# 13_1_Port-Backplane.net
KiCad netlist of a schematic drawn in EAGLE
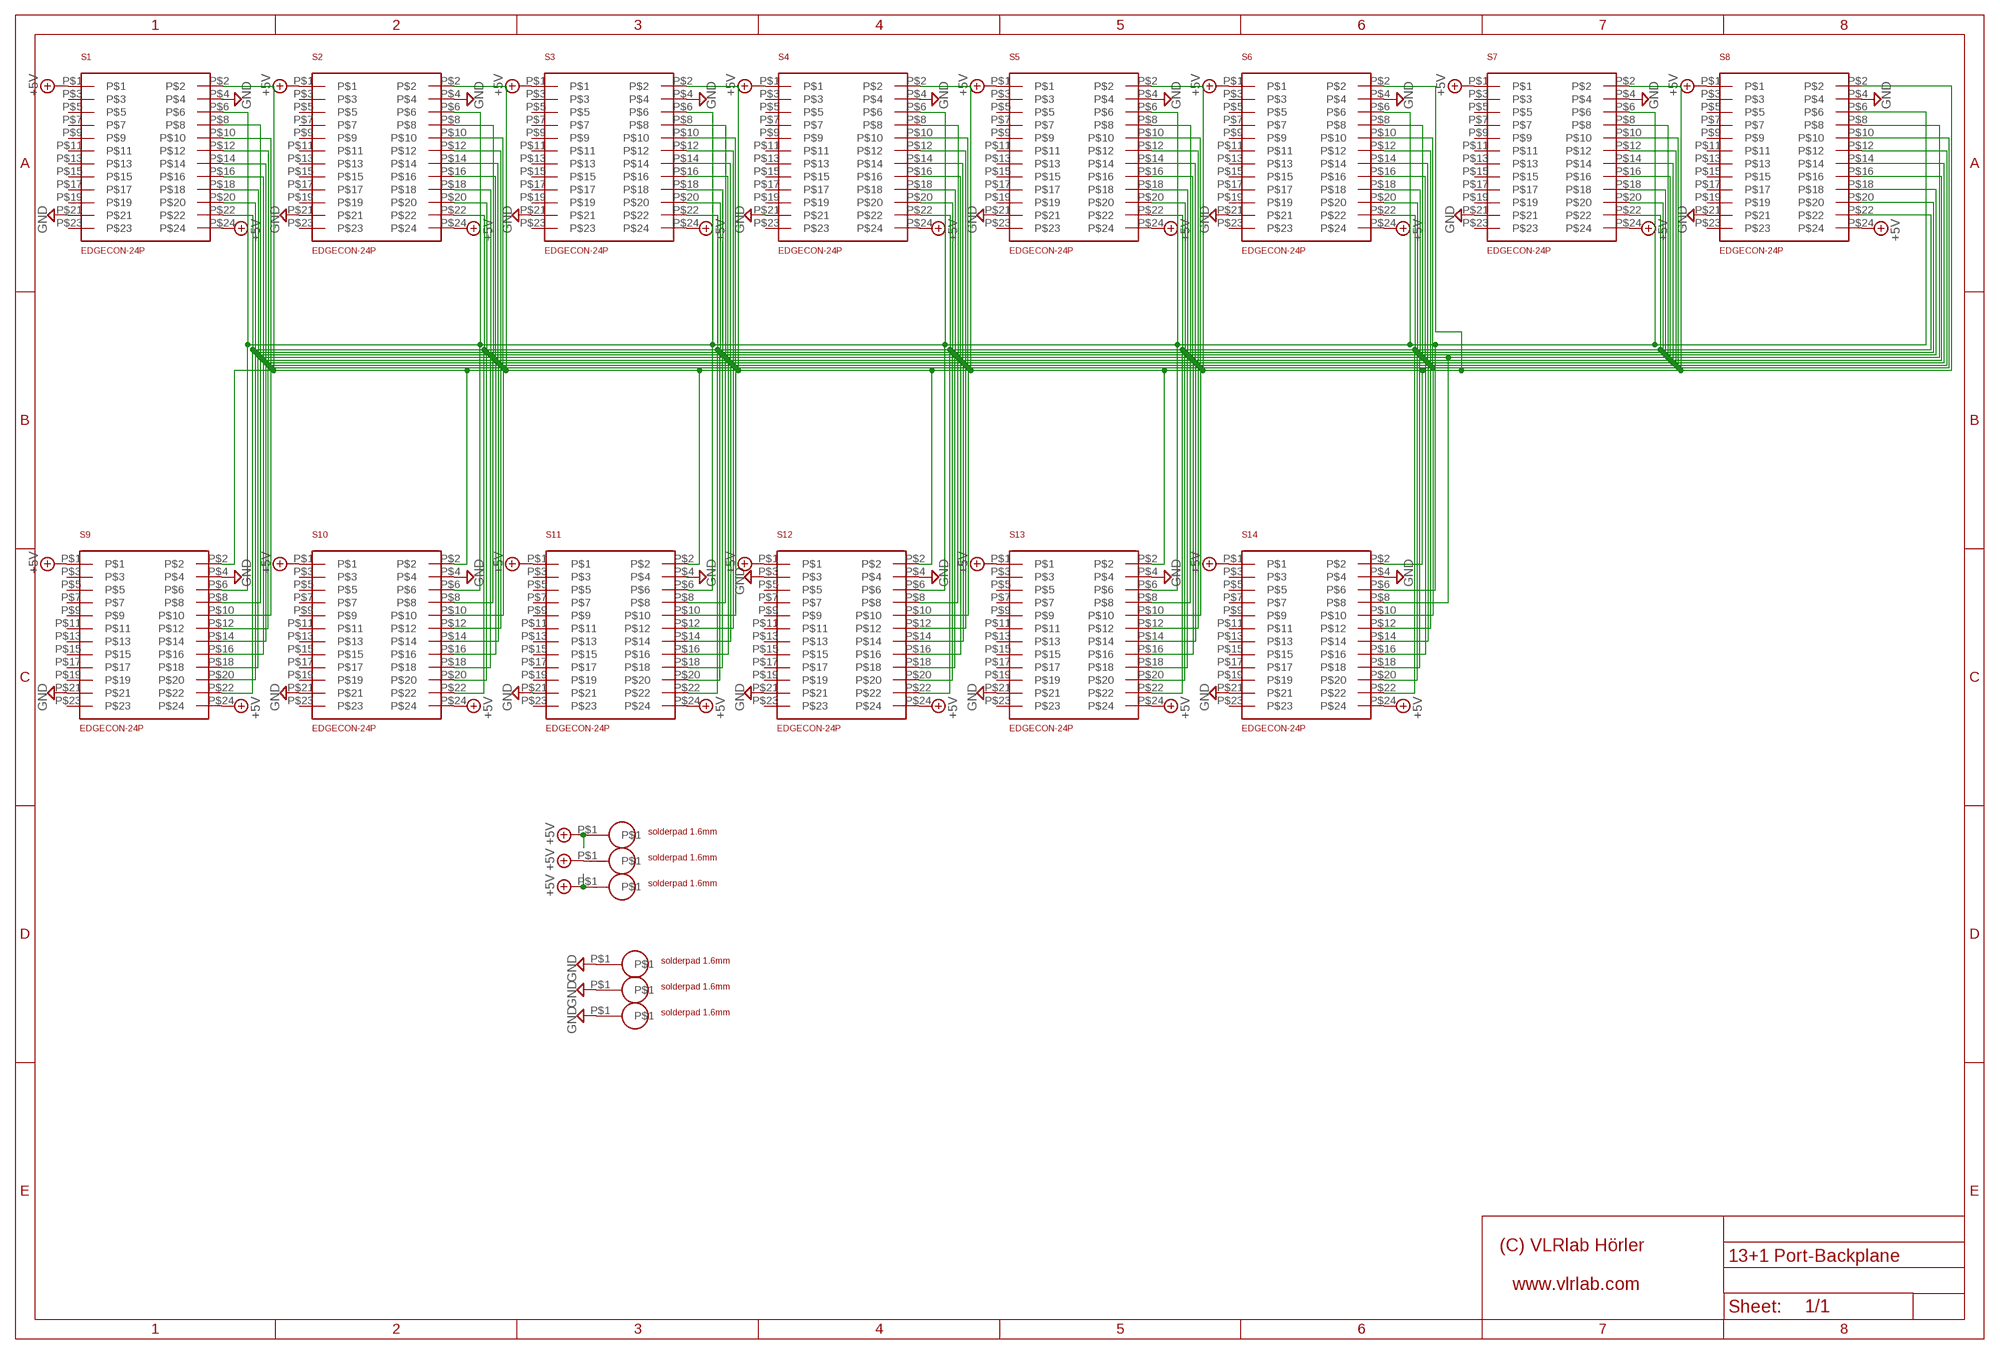
[diagram p0: schematic, sheet 1]

(export (version "E")
  (design (tool "Eeschema 10.0.6"))
  (components
    (comp (ref "S1")
      (value "EDGECON-24P")
      (footprint "eagle-import:LEDSEE-BOARDCONN24PIN")
      (libsource (lib "eagle-import") (part "EDGECON-24P"))
    )
    (comp (ref "S2")
      (value "EDGECON-24P")
      (footprint "eagle-import:LEDSEE-BOARDCONN24PIN")
      (libsource (lib "eagle-import") (part "EDGECON-24P"))
    )
    (comp (ref "S3")
      (value "EDGECON-24P")
      (footprint "eagle-import:LEDSEE-BOARDCONN24PIN")
      (libsource (lib "eagle-import") (part "EDGECON-24P"))
    )
    (comp (ref "S4")
      (value "EDGECON-24P")
      (footprint "eagle-import:LEDSEE-BOARDCONN24PIN")
      (libsource (lib "eagle-import") (part "EDGECON-24P"))
    )
    (comp (ref "S5")
      (value "EDGECON-24P")
      (footprint "eagle-import:LEDSEE-BOARDCONN24PIN")
      (libsource (lib "eagle-import") (part "EDGECON-24P"))
    )
    (comp (ref "S6")
      (value "EDGECON-24P")
      (footprint "eagle-import:LEDSEE-BOARDCONN24PIN")
      (libsource (lib "eagle-import") (part "EDGECON-24P"))
    )
    (comp (ref "S7")
      (value "EDGECON-24P")
      (footprint "eagle-import:LEDSEE-BOARDCONN24PIN")
      (libsource (lib "eagle-import") (part "EDGECON-24P"))
    )
    (comp (ref "S8")
      (value "EDGECON-24P")
      (footprint "eagle-import:LEDSEE-BOARDCONN24PIN")
      (libsource (lib "eagle-import") (part "EDGECON-24P"))
    )
    (comp (ref "S9")
      (value "EDGECON-24P")
      (footprint "eagle-import:LEDSEE-BOARDCONN24PIN")
      (libsource (lib "eagle-import") (part "EDGECON-24P"))
    )
    (comp (ref "S10")
      (value "EDGECON-24P")
      (footprint "eagle-import:LEDSEE-BOARDCONN24PIN")
      (libsource (lib "eagle-import") (part "EDGECON-24P"))
    )
    (comp (ref "S11")
      (value "EDGECON-24P")
      (footprint "eagle-import:LEDSEE-BOARDCONN24PIN")
      (libsource (lib "eagle-import") (part "EDGECON-24P"))
    )
    (comp (ref "S12")
      (value "EDGECON-24P")
      (footprint "eagle-import:LEDSEE-BOARDCONN24PIN")
      (libsource (lib "eagle-import") (part "EDGECON-24P"))
    )
    (comp (ref "S13")
      (value "EDGECON-24P")
      (footprint "eagle-import:LEDSEE-BOARDCONN24PIN")
      (libsource (lib "eagle-import") (part "EDGECON-24P"))
    )
    (comp (ref "S14")
      (value "EDGECON-24P")
      (footprint "eagle-import:LEDSEE-BOARDCONN24PIN")
      (libsource (lib "eagle-import") (part "EDGECON-24P"))
    )
    (comp (ref "U$6")
      (value "SOLPAD-1,6MM")
      (footprint "eagle-import:SOLDERPAD1.5MM")
      (libsource (lib "eagle-import") (part "SOLPAD-1,6MM"))
    )
    (comp (ref "U$7")
      (value "SOLPAD-1,6MM")
      (footprint "eagle-import:SOLDERPAD1.5MM")
      (libsource (lib "eagle-import") (part "SOLPAD-1,6MM"))
    )
    (comp (ref "U$8")
      (value "SOLPAD-1,6MM")
      (footprint "eagle-import:SOLDERPAD1.5MM")
      (libsource (lib "eagle-import") (part "SOLPAD-1,6MM"))
    )
    (comp (ref "U$9")
      (value "SOLPAD-1,6MM")
      (footprint "eagle-import:SOLDERPAD1.5MM")
      (libsource (lib "eagle-import") (part "SOLPAD-1,6MM"))
    )
    (comp (ref "U$10")
      (value "SOLPAD-1,6MM")
      (footprint "eagle-import:SOLDERPAD1.5MM")
      (libsource (lib "eagle-import") (part "SOLPAD-1,6MM"))
    )
    (comp (ref "U$11")
      (value "SOLPAD-1,6MM")
      (footprint "eagle-import:SOLDERPAD1.5MM")
      (libsource (lib "eagle-import") (part "SOLPAD-1,6MM"))
    )
  )
  (nets
    (net (code "1") (name "+5V") (class "Default")
      (node (ref "S1") (pin "P$1") (pinfunction "P$1_P$1") (pintype "bidirectional"))
      (node (ref "S1") (pin "P$24") (pinfunction "P$24_P$24") (pintype "bidirectional"))
      (node (ref "S10") (pin "P$1") (pinfunction "P$1_P$1") (pintype "bidirectional"))
      (node (ref "S10") (pin "P$24") (pinfunction "P$24_P$24") (pintype "bidirectional"))
      (node (ref "S11") (pin "P$1") (pinfunction "P$1_P$1") (pintype "bidirectional"))
      (node (ref "S11") (pin "P$24") (pinfunction "P$24_P$24") (pintype "bidirectional"))
      (node (ref "S12") (pin "P$1") (pinfunction "P$1_P$1") (pintype "bidirectional"))
      (node (ref "S12") (pin "P$24") (pinfunction "P$24_P$24") (pintype "bidirectional"))
      (node (ref "S13") (pin "P$1") (pinfunction "P$1_P$1") (pintype "bidirectional"))
      (node (ref "S13") (pin "P$24") (pinfunction "P$24_P$24") (pintype "bidirectional"))
      (node (ref "S14") (pin "P$1") (pinfunction "P$1_P$1") (pintype "bidirectional"))
      (node (ref "S14") (pin "P$24") (pinfunction "P$24_P$24") (pintype "bidirectional"))
      (node (ref "S2") (pin "P$1") (pinfunction "P$1_P$1") (pintype "bidirectional"))
      (node (ref "S2") (pin "P$24") (pinfunction "P$24_P$24") (pintype "bidirectional"))
      (node (ref "S3") (pin "P$1") (pinfunction "P$1_P$1") (pintype "bidirectional"))
      (node (ref "S3") (pin "P$24") (pinfunction "P$24_P$24") (pintype "bidirectional"))
      (node (ref "S4") (pin "P$1") (pinfunction "P$1_P$1") (pintype "bidirectional"))
      (node (ref "S4") (pin "P$24") (pinfunction "P$24_P$24") (pintype "bidirectional"))
      (node (ref "S5") (pin "P$1") (pinfunction "P$1_P$1") (pintype "bidirectional"))
      (node (ref "S5") (pin "P$24") (pinfunction "P$24_P$24") (pintype "bidirectional"))
      (node (ref "S6") (pin "P$1") (pinfunction "P$1_P$1") (pintype "bidirectional"))
      (node (ref "S6") (pin "P$24") (pinfunction "P$24_P$24") (pintype "bidirectional"))
      (node (ref "S7") (pin "P$1") (pinfunction "P$1_P$1") (pintype "bidirectional"))
      (node (ref "S7") (pin "P$24") (pinfunction "P$24_P$24") (pintype "bidirectional"))
      (node (ref "S8") (pin "P$1") (pinfunction "P$1_P$1") (pintype "bidirectional"))
      (node (ref "S8") (pin "P$24") (pinfunction "P$24_P$24") (pintype "bidirectional"))
      (node (ref "S9") (pin "P$1") (pinfunction "P$1_P$1") (pintype "bidirectional"))
      (node (ref "S9") (pin "P$24") (pinfunction "P$24_P$24") (pintype "bidirectional"))
      (node (ref "U$6") (pin "P$1") (pinfunction "P$1_P$1") (pintype "bidirectional"))
      (node (ref "U$7") (pin "P$1") (pinfunction "P$1_P$1") (pintype "bidirectional"))
      (node (ref "U$9") (pin "P$1") (pinfunction "P$1_P$1") (pintype "bidirectional"))
    )
    (net (code "2") (name "GND") (class "Default")
      (node (ref "S1") (pin "P$21") (pinfunction "P$21_P$21") (pintype "bidirectional"))
      (node (ref "S1") (pin "P$4") (pinfunction "P$4_P$4") (pintype "bidirectional"))
      (node (ref "S10") (pin "P$21") (pinfunction "P$21_P$21") (pintype "bidirectional"))
      (node (ref "S10") (pin "P$4") (pinfunction "P$4_P$4") (pintype "bidirectional"))
      (node (ref "S11") (pin "P$21") (pinfunction "P$21_P$21") (pintype "bidirectional"))
      (node (ref "S11") (pin "P$4") (pinfunction "P$4_P$4") (pintype "bidirectional"))
      (node (ref "S12") (pin "P$21") (pinfunction "P$21_P$21") (pintype "bidirectional"))
      (node (ref "S12") (pin "P$3") (pinfunction "P$3_P$3") (pintype "bidirectional"))
      (node (ref "S12") (pin "P$4") (pinfunction "P$4_P$4") (pintype "bidirectional"))
      (node (ref "S13") (pin "P$21") (pinfunction "P$21_P$21") (pintype "bidirectional"))
      (node (ref "S13") (pin "P$4") (pinfunction "P$4_P$4") (pintype "bidirectional"))
      (node (ref "S14") (pin "P$21") (pinfunction "P$21_P$21") (pintype "bidirectional"))
      (node (ref "S14") (pin "P$4") (pinfunction "P$4_P$4") (pintype "bidirectional"))
      (node (ref "S2") (pin "P$21") (pinfunction "P$21_P$21") (pintype "bidirectional"))
      (node (ref "S2") (pin "P$4") (pinfunction "P$4_P$4") (pintype "bidirectional"))
      (node (ref "S3") (pin "P$21") (pinfunction "P$21_P$21") (pintype "bidirectional"))
      (node (ref "S3") (pin "P$4") (pinfunction "P$4_P$4") (pintype "bidirectional"))
      (node (ref "S4") (pin "P$21") (pinfunction "P$21_P$21") (pintype "bidirectional"))
      (node (ref "S4") (pin "P$4") (pinfunction "P$4_P$4") (pintype "bidirectional"))
      (node (ref "S5") (pin "P$21") (pinfunction "P$21_P$21") (pintype "bidirectional"))
      (node (ref "S5") (pin "P$4") (pinfunction "P$4_P$4") (pintype "bidirectional"))
      (node (ref "S6") (pin "P$21") (pinfunction "P$21_P$21") (pintype "bidirectional"))
      (node (ref "S6") (pin "P$4") (pinfunction "P$4_P$4") (pintype "bidirectional"))
      (node (ref "S7") (pin "P$21") (pinfunction "P$21_P$21") (pintype "bidirectional"))
      (node (ref "S7") (pin "P$4") (pinfunction "P$4_P$4") (pintype "bidirectional"))
      (node (ref "S8") (pin "P$21") (pinfunction "P$21_P$21") (pintype "bidirectional"))
      (node (ref "S8") (pin "P$4") (pinfunction "P$4_P$4") (pintype "bidirectional"))
      (node (ref "S9") (pin "P$21") (pinfunction "P$21_P$21") (pintype "bidirectional"))
      (node (ref "S9") (pin "P$4") (pinfunction "P$4_P$4") (pintype "bidirectional"))
      (node (ref "U$10") (pin "P$1") (pinfunction "P$1_P$1") (pintype "bidirectional"))
      (node (ref "U$11") (pin "P$1") (pinfunction "P$1_P$1") (pintype "bidirectional"))
      (node (ref "U$8") (pin "P$1") (pinfunction "P$1_P$1") (pintype "bidirectional"))
    )
    (net (code "3") (name "Net-(S1-PadP$2)") (class "Default")
      (node (ref "S1") (pin "P$2") (pinfunction "P$2_P$2") (pintype "bidirectional"))
      (node (ref "S10") (pin "P$2") (pinfunction "P$2_P$2") (pintype "bidirectional"))
      (node (ref "S11") (pin "P$2") (pinfunction "P$2_P$2") (pintype "bidirectional"))
      (node (ref "S12") (pin "P$2") (pinfunction "P$2_P$2") (pintype "bidirectional"))
      (node (ref "S13") (pin "P$2") (pinfunction "P$2_P$2") (pintype "bidirectional"))
      (node (ref "S14") (pin "P$2") (pinfunction "P$2_P$2") (pintype "bidirectional"))
      (node (ref "S2") (pin "P$2") (pinfunction "P$2_P$2") (pintype "bidirectional"))
      (node (ref "S3") (pin "P$2") (pinfunction "P$2_P$2") (pintype "bidirectional"))
      (node (ref "S4") (pin "P$2") (pinfunction "P$2_P$2") (pintype "bidirectional"))
      (node (ref "S5") (pin "P$2") (pinfunction "P$2_P$2") (pintype "bidirectional"))
      (node (ref "S6") (pin "P$2") (pinfunction "P$2_P$2") (pintype "bidirectional"))
      (node (ref "S7") (pin "P$2") (pinfunction "P$2_P$2") (pintype "bidirectional"))
      (node (ref "S8") (pin "P$2") (pinfunction "P$2_P$2") (pintype "bidirectional"))
      (node (ref "S9") (pin "P$2") (pinfunction "P$2_P$2") (pintype "bidirectional"))
    )
    (net (code "4") (name "Net-(S1-PadP$6)") (class "Default")
      (node (ref "S1") (pin "P$6") (pinfunction "P$6_P$6") (pintype "bidirectional"))
      (node (ref "S10") (pin "P$6") (pinfunction "P$6_P$6") (pintype "bidirectional"))
      (node (ref "S11") (pin "P$6") (pinfunction "P$6_P$6") (pintype "bidirectional"))
      (node (ref "S12") (pin "P$6") (pinfunction "P$6_P$6") (pintype "bidirectional"))
      (node (ref "S13") (pin "P$6") (pinfunction "P$6_P$6") (pintype "bidirectional"))
      (node (ref "S14") (pin "P$6") (pinfunction "P$6_P$6") (pintype "bidirectional"))
      (node (ref "S2") (pin "P$6") (pinfunction "P$6_P$6") (pintype "bidirectional"))
      (node (ref "S3") (pin "P$6") (pinfunction "P$6_P$6") (pintype "bidirectional"))
      (node (ref "S4") (pin "P$6") (pinfunction "P$6_P$6") (pintype "bidirectional"))
      (node (ref "S5") (pin "P$6") (pinfunction "P$6_P$6") (pintype "bidirectional"))
      (node (ref "S6") (pin "P$6") (pinfunction "P$6_P$6") (pintype "bidirectional"))
      (node (ref "S7") (pin "P$6") (pinfunction "P$6_P$6") (pintype "bidirectional"))
      (node (ref "S8") (pin "P$6") (pinfunction "P$6_P$6") (pintype "bidirectional"))
      (node (ref "S9") (pin "P$6") (pinfunction "P$6_P$6") (pintype "bidirectional"))
    )
    (net (code "5") (name "Net-(S1-PadP$8)") (class "Default")
      (node (ref "S1") (pin "P$8") (pinfunction "P$8_P$8") (pintype "bidirectional"))
      (node (ref "S10") (pin "P$8") (pinfunction "P$8_P$8") (pintype "bidirectional"))
      (node (ref "S11") (pin "P$8") (pinfunction "P$8_P$8") (pintype "bidirectional"))
      (node (ref "S12") (pin "P$8") (pinfunction "P$8_P$8") (pintype "bidirectional"))
      (node (ref "S13") (pin "P$8") (pinfunction "P$8_P$8") (pintype "bidirectional"))
      (node (ref "S14") (pin "P$8") (pinfunction "P$8_P$8") (pintype "bidirectional"))
      (node (ref "S2") (pin "P$8") (pinfunction "P$8_P$8") (pintype "bidirectional"))
      (node (ref "S3") (pin "P$8") (pinfunction "P$8_P$8") (pintype "bidirectional"))
      (node (ref "S4") (pin "P$8") (pinfunction "P$8_P$8") (pintype "bidirectional"))
      (node (ref "S5") (pin "P$8") (pinfunction "P$8_P$8") (pintype "bidirectional"))
      (node (ref "S6") (pin "P$8") (pinfunction "P$8_P$8") (pintype "bidirectional"))
      (node (ref "S7") (pin "P$8") (pinfunction "P$8_P$8") (pintype "bidirectional"))
      (node (ref "S8") (pin "P$8") (pinfunction "P$8_P$8") (pintype "bidirectional"))
      (node (ref "S9") (pin "P$8") (pinfunction "P$8_P$8") (pintype "bidirectional"))
    )
    (net (code "6") (name "Net-(S1-PadP$10)") (class "Default")
      (node (ref "S1") (pin "P$10") (pinfunction "P$10_P$10") (pintype "bidirectional"))
      (node (ref "S10") (pin "P$10") (pinfunction "P$10_P$10") (pintype "bidirectional"))
      (node (ref "S11") (pin "P$10") (pinfunction "P$10_P$10") (pintype "bidirectional"))
      (node (ref "S12") (pin "P$10") (pinfunction "P$10_P$10") (pintype "bidirectional"))
      (node (ref "S13") (pin "P$10") (pinfunction "P$10_P$10") (pintype "bidirectional"))
      (node (ref "S14") (pin "P$10") (pinfunction "P$10_P$10") (pintype "bidirectional"))
      (node (ref "S2") (pin "P$10") (pinfunction "P$10_P$10") (pintype "bidirectional"))
      (node (ref "S3") (pin "P$10") (pinfunction "P$10_P$10") (pintype "bidirectional"))
      (node (ref "S4") (pin "P$10") (pinfunction "P$10_P$10") (pintype "bidirectional"))
      (node (ref "S5") (pin "P$10") (pinfunction "P$10_P$10") (pintype "bidirectional"))
      (node (ref "S6") (pin "P$10") (pinfunction "P$10_P$10") (pintype "bidirectional"))
      (node (ref "S7") (pin "P$10") (pinfunction "P$10_P$10") (pintype "bidirectional"))
      (node (ref "S8") (pin "P$10") (pinfunction "P$10_P$10") (pintype "bidirectional"))
      (node (ref "S9") (pin "P$10") (pinfunction "P$10_P$10") (pintype "bidirectional"))
    )
    (net (code "7") (name "Net-(S1-PadP$12)") (class "Default")
      (node (ref "S1") (pin "P$12") (pinfunction "P$12_P$12") (pintype "bidirectional"))
      (node (ref "S10") (pin "P$12") (pinfunction "P$12_P$12") (pintype "bidirectional"))
      (node (ref "S11") (pin "P$12") (pinfunction "P$12_P$12") (pintype "bidirectional"))
      (node (ref "S12") (pin "P$12") (pinfunction "P$12_P$12") (pintype "bidirectional"))
      (node (ref "S13") (pin "P$12") (pinfunction "P$12_P$12") (pintype "bidirectional"))
      (node (ref "S14") (pin "P$12") (pinfunction "P$12_P$12") (pintype "bidirectional"))
      (node (ref "S2") (pin "P$12") (pinfunction "P$12_P$12") (pintype "bidirectional"))
      (node (ref "S3") (pin "P$12") (pinfunction "P$12_P$12") (pintype "bidirectional"))
      (node (ref "S4") (pin "P$12") (pinfunction "P$12_P$12") (pintype "bidirectional"))
      (node (ref "S5") (pin "P$12") (pinfunction "P$12_P$12") (pintype "bidirectional"))
      (node (ref "S6") (pin "P$12") (pinfunction "P$12_P$12") (pintype "bidirectional"))
      (node (ref "S7") (pin "P$12") (pinfunction "P$12_P$12") (pintype "bidirectional"))
      (node (ref "S8") (pin "P$12") (pinfunction "P$12_P$12") (pintype "bidirectional"))
      (node (ref "S9") (pin "P$12") (pinfunction "P$12_P$12") (pintype "bidirectional"))
    )
    (net (code "8") (name "Net-(S1-PadP$14)") (class "Default")
      (node (ref "S1") (pin "P$14") (pinfunction "P$14_P$14") (pintype "bidirectional"))
      (node (ref "S10") (pin "P$14") (pinfunction "P$14_P$14") (pintype "bidirectional"))
      (node (ref "S11") (pin "P$14") (pinfunction "P$14_P$14") (pintype "bidirectional"))
      (node (ref "S12") (pin "P$14") (pinfunction "P$14_P$14") (pintype "bidirectional"))
      (node (ref "S13") (pin "P$14") (pinfunction "P$14_P$14") (pintype "bidirectional"))
      (node (ref "S14") (pin "P$14") (pinfunction "P$14_P$14") (pintype "bidirectional"))
      (node (ref "S2") (pin "P$14") (pinfunction "P$14_P$14") (pintype "bidirectional"))
      (node (ref "S3") (pin "P$14") (pinfunction "P$14_P$14") (pintype "bidirectional"))
      (node (ref "S4") (pin "P$14") (pinfunction "P$14_P$14") (pintype "bidirectional"))
      (node (ref "S5") (pin "P$14") (pinfunction "P$14_P$14") (pintype "bidirectional"))
      (node (ref "S6") (pin "P$14") (pinfunction "P$14_P$14") (pintype "bidirectional"))
      (node (ref "S7") (pin "P$14") (pinfunction "P$14_P$14") (pintype "bidirectional"))
      (node (ref "S8") (pin "P$14") (pinfunction "P$14_P$14") (pintype "bidirectional"))
      (node (ref "S9") (pin "P$14") (pinfunction "P$14_P$14") (pintype "bidirectional"))
    )
    (net (code "9") (name "Net-(S1-PadP$16)") (class "Default")
      (node (ref "S1") (pin "P$16") (pinfunction "P$16_P$16") (pintype "bidirectional"))
      (node (ref "S10") (pin "P$16") (pinfunction "P$16_P$16") (pintype "bidirectional"))
      (node (ref "S11") (pin "P$16") (pinfunction "P$16_P$16") (pintype "bidirectional"))
      (node (ref "S12") (pin "P$16") (pinfunction "P$16_P$16") (pintype "bidirectional"))
      (node (ref "S13") (pin "P$16") (pinfunction "P$16_P$16") (pintype "bidirectional"))
      (node (ref "S14") (pin "P$16") (pinfunction "P$16_P$16") (pintype "bidirectional"))
      (node (ref "S2") (pin "P$16") (pinfunction "P$16_P$16") (pintype "bidirectional"))
      (node (ref "S3") (pin "P$16") (pinfunction "P$16_P$16") (pintype "bidirectional"))
      (node (ref "S4") (pin "P$16") (pinfunction "P$16_P$16") (pintype "bidirectional"))
      (node (ref "S5") (pin "P$16") (pinfunction "P$16_P$16") (pintype "bidirectional"))
      (node (ref "S6") (pin "P$16") (pinfunction "P$16_P$16") (pintype "bidirectional"))
      (node (ref "S7") (pin "P$16") (pinfunction "P$16_P$16") (pintype "bidirectional"))
      (node (ref "S8") (pin "P$16") (pinfunction "P$16_P$16") (pintype "bidirectional"))
      (node (ref "S9") (pin "P$16") (pinfunction "P$16_P$16") (pintype "bidirectional"))
    )
    (net (code "10") (name "Net-(S1-PadP$18)") (class "Default")
      (node (ref "S1") (pin "P$18") (pinfunction "P$18_P$18") (pintype "bidirectional"))
      (node (ref "S10") (pin "P$18") (pinfunction "P$18_P$18") (pintype "bidirectional"))
      (node (ref "S11") (pin "P$18") (pinfunction "P$18_P$18") (pintype "bidirectional"))
      (node (ref "S12") (pin "P$18") (pinfunction "P$18_P$18") (pintype "bidirectional"))
      (node (ref "S13") (pin "P$18") (pinfunction "P$18_P$18") (pintype "bidirectional"))
      (node (ref "S14") (pin "P$18") (pinfunction "P$18_P$18") (pintype "bidirectional"))
      (node (ref "S2") (pin "P$18") (pinfunction "P$18_P$18") (pintype "bidirectional"))
      (node (ref "S3") (pin "P$18") (pinfunction "P$18_P$18") (pintype "bidirectional"))
      (node (ref "S4") (pin "P$18") (pinfunction "P$18_P$18") (pintype "bidirectional"))
      (node (ref "S5") (pin "P$18") (pinfunction "P$18_P$18") (pintype "bidirectional"))
      (node (ref "S6") (pin "P$18") (pinfunction "P$18_P$18") (pintype "bidirectional"))
      (node (ref "S7") (pin "P$18") (pinfunction "P$18_P$18") (pintype "bidirectional"))
      (node (ref "S8") (pin "P$18") (pinfunction "P$18_P$18") (pintype "bidirectional"))
      (node (ref "S9") (pin "P$18") (pinfunction "P$18_P$18") (pintype "bidirectional"))
    )
    (net (code "11") (name "Net-(S1-PadP$20)") (class "Default")
      (node (ref "S1") (pin "P$20") (pinfunction "P$20_P$20") (pintype "bidirectional"))
      (node (ref "S10") (pin "P$20") (pinfunction "P$20_P$20") (pintype "bidirectional"))
      (node (ref "S11") (pin "P$20") (pinfunction "P$20_P$20") (pintype "bidirectional"))
      (node (ref "S12") (pin "P$20") (pinfunction "P$20_P$20") (pintype "bidirectional"))
      (node (ref "S13") (pin "P$20") (pinfunction "P$20_P$20") (pintype "bidirectional"))
      (node (ref "S14") (pin "P$20") (pinfunction "P$20_P$20") (pintype "bidirectional"))
      (node (ref "S2") (pin "P$20") (pinfunction "P$20_P$20") (pintype "bidirectional"))
      (node (ref "S3") (pin "P$20") (pinfunction "P$20_P$20") (pintype "bidirectional"))
      (node (ref "S4") (pin "P$20") (pinfunction "P$20_P$20") (pintype "bidirectional"))
      (node (ref "S5") (pin "P$20") (pinfunction "P$20_P$20") (pintype "bidirectional"))
      (node (ref "S6") (pin "P$20") (pinfunction "P$20_P$20") (pintype "bidirectional"))
      (node (ref "S7") (pin "P$20") (pinfunction "P$20_P$20") (pintype "bidirectional"))
      (node (ref "S8") (pin "P$20") (pinfunction "P$20_P$20") (pintype "bidirectional"))
      (node (ref "S9") (pin "P$20") (pinfunction "P$20_P$20") (pintype "bidirectional"))
    )
    (net (code "12") (name "Net-(S1-PadP$22)") (class "Default")
      (node (ref "S1") (pin "P$22") (pinfunction "P$22_P$22") (pintype "bidirectional"))
      (node (ref "S10") (pin "P$22") (pinfunction "P$22_P$22") (pintype "bidirectional"))
      (node (ref "S11") (pin "P$22") (pinfunction "P$22_P$22") (pintype "bidirectional"))
      (node (ref "S12") (pin "P$22") (pinfunction "P$22_P$22") (pintype "bidirectional"))
      (node (ref "S13") (pin "P$22") (pinfunction "P$22_P$22") (pintype "bidirectional"))
      (node (ref "S14") (pin "P$22") (pinfunction "P$22_P$22") (pintype "bidirectional"))
      (node (ref "S2") (pin "P$22") (pinfunction "P$22_P$22") (pintype "bidirectional"))
      (node (ref "S3") (pin "P$22") (pinfunction "P$22_P$22") (pintype "bidirectional"))
      (node (ref "S4") (pin "P$22") (pinfunction "P$22_P$22") (pintype "bidirectional"))
      (node (ref "S5") (pin "P$22") (pinfunction "P$22_P$22") (pintype "bidirectional"))
      (node (ref "S6") (pin "P$22") (pinfunction "P$22_P$22") (pintype "bidirectional"))
      (node (ref "S7") (pin "P$22") (pinfunction "P$22_P$22") (pintype "bidirectional"))
      (node (ref "S8") (pin "P$22") (pinfunction "P$22_P$22") (pintype "bidirectional"))
      (node (ref "S9") (pin "P$22") (pinfunction "P$22_P$22") (pintype "bidirectional"))
    )
    (net (code "13") (name "unconnected-(S1-PadP$3)") (class "Default")
      (node (ref "S1") (pin "P$3") (pinfunction "P$3_P$3") (pintype "bidirectional"))
    )
    (net (code "14") (name "unconnected-(S1-PadP$5)") (class "Default")
      (node (ref "S1") (pin "P$5") (pinfunction "P$5_P$5") (pintype "bidirectional"))
    )
    (net (code "15") (name "unconnected-(S1-PadP$7)") (class "Default")
      (node (ref "S1") (pin "P$7") (pinfunction "P$7_P$7") (pintype "bidirectional"))
    )
    (net (code "16") (name "unconnected-(S1-PadP$9)") (class "Default")
      (node (ref "S1") (pin "P$9") (pinfunction "P$9_P$9") (pintype "bidirectional"))
    )
    (net (code "17") (name "unconnected-(S1-PadP$11)") (class "Default")
      (node (ref "S1") (pin "P$11") (pinfunction "P$11_P$11") (pintype "bidirectional"))
    )
    (net (code "18") (name "unconnected-(S1-PadP$13)") (class "Default")
      (node (ref "S1") (pin "P$13") (pinfunction "P$13_P$13") (pintype "bidirectional"))
    )
    (net (code "19") (name "unconnected-(S1-PadP$15)") (class "Default")
      (node (ref "S1") (pin "P$15") (pinfunction "P$15_P$15") (pintype "bidirectional"))
    )
    (net (code "20") (name "unconnected-(S1-PadP$17)") (class "Default")
      (node (ref "S1") (pin "P$17") (pinfunction "P$17_P$17") (pintype "bidirectional"))
    )
    (net (code "21") (name "unconnected-(S1-PadP$19)") (class "Default")
      (node (ref "S1") (pin "P$19") (pinfunction "P$19_P$19") (pintype "bidirectional"))
    )
    (net (code "22") (name "unconnected-(S1-PadP$23)") (class "Default")
      (node (ref "S1") (pin "P$23") (pinfunction "P$23_P$23") (pintype "bidirectional"))
    )
    (net (code "23") (name "unconnected-(S2-PadP$3)") (class "Default")
      (node (ref "S2") (pin "P$3") (pinfunction "P$3_P$3") (pintype "bidirectional"))
    )
    (net (code "24") (name "unconnected-(S2-PadP$5)") (class "Default")
      (node (ref "S2") (pin "P$5") (pinfunction "P$5_P$5") (pintype "bidirectional"))
    )
    (net (code "25") (name "unconnected-(S2-PadP$7)") (class "Default")
      (node (ref "S2") (pin "P$7") (pinfunction "P$7_P$7") (pintype "bidirectional"))
    )
    (net (code "26") (name "unconnected-(S2-PadP$9)") (class "Default")
      (node (ref "S2") (pin "P$9") (pinfunction "P$9_P$9") (pintype "bidirectional"))
    )
    (net (code "27") (name "unconnected-(S2-PadP$11)") (class "Default")
      (node (ref "S2") (pin "P$11") (pinfunction "P$11_P$11") (pintype "bidirectional"))
    )
    (net (code "28") (name "unconnected-(S2-PadP$13)") (class "Default")
      (node (ref "S2") (pin "P$13") (pinfunction "P$13_P$13") (pintype "bidirectional"))
    )
    (net (code "29") (name "unconnected-(S2-PadP$15)") (class "Default")
      (node (ref "S2") (pin "P$15") (pinfunction "P$15_P$15") (pintype "bidirectional"))
    )
    (net (code "30") (name "unconnected-(S2-PadP$17)") (class "Default")
      (node (ref "S2") (pin "P$17") (pinfunction "P$17_P$17") (pintype "bidirectional"))
    )
    (net (code "31") (name "unconnected-(S2-PadP$19)") (class "Default")
      (node (ref "S2") (pin "P$19") (pinfunction "P$19_P$19") (pintype "bidirectional"))
    )
    (net (code "32") (name "unconnected-(S2-PadP$23)") (class "Default")
      (node (ref "S2") (pin "P$23") (pinfunction "P$23_P$23") (pintype "bidirectional"))
    )
    (net (code "33") (name "unconnected-(S3-PadP$3)") (class "Default")
      (node (ref "S3") (pin "P$3") (pinfunction "P$3_P$3") (pintype "bidirectional"))
    )
    (net (code "34") (name "unconnected-(S3-PadP$5)") (class "Default")
      (node (ref "S3") (pin "P$5") (pinfunction "P$5_P$5") (pintype "bidirectional"))
    )
    (net (code "35") (name "unconnected-(S3-PadP$7)") (class "Default")
      (node (ref "S3") (pin "P$7") (pinfunction "P$7_P$7") (pintype "bidirectional"))
    )
    (net (code "36") (name "unconnected-(S3-PadP$9)") (class "Default")
      (node (ref "S3") (pin "P$9") (pinfunction "P$9_P$9") (pintype "bidirectional"))
    )
    (net (code "37") (name "unconnected-(S3-PadP$11)") (class "Default")
      (node (ref "S3") (pin "P$11") (pinfunction "P$11_P$11") (pintype "bidirectional"))
    )
    (net (code "38") (name "unconnected-(S3-PadP$13)") (class "Default")
      (node (ref "S3") (pin "P$13") (pinfunction "P$13_P$13") (pintype "bidirectional"))
    )
    (net (code "39") (name "unconnected-(S3-PadP$15)") (class "Default")
      (node (ref "S3") (pin "P$15") (pinfunction "P$15_P$15") (pintype "bidirectional"))
    )
    (net (code "40") (name "unconnected-(S3-PadP$17)") (class "Default")
      (node (ref "S3") (pin "P$17") (pinfunction "P$17_P$17") (pintype "bidirectional"))
    )
    (net (code "41") (name "unconnected-(S3-PadP$19)") (class "Default")
      (node (ref "S3") (pin "P$19") (pinfunction "P$19_P$19") (pintype "bidirectional"))
    )
    (net (code "42") (name "unconnected-(S3-PadP$23)") (class "Default")
      (node (ref "S3") (pin "P$23") (pinfunction "P$23_P$23") (pintype "bidirectional"))
    )
    (net (code "43") (name "unconnected-(S4-PadP$3)") (class "Default")
      (node (ref "S4") (pin "P$3") (pinfunction "P$3_P$3") (pintype "bidirectional"))
    )
    (net (code "44") (name "unconnected-(S4-PadP$5)") (class "Default")
      (node (ref "S4") (pin "P$5") (pinfunction "P$5_P$5") (pintype "bidirectional"))
    )
    (net (code "45") (name "unconnected-(S4-PadP$7)") (class "Default")
      (node (ref "S4") (pin "P$7") (pinfunction "P$7_P$7") (pintype "bidirectional"))
    )
    (net (code "46") (name "unconnected-(S4-PadP$9)") (class "Default")
      (node (ref "S4") (pin "P$9") (pinfunction "P$9_P$9") (pintype "bidirectional"))
    )
    (net (code "47") (name "unconnected-(S4-PadP$11)") (class "Default")
      (node (ref "S4") (pin "P$11") (pinfunction "P$11_P$11") (pintype "bidirectional"))
    )
    (net (code "48") (name "unconnected-(S4-PadP$13)") (class "Default")
      (node (ref "S4") (pin "P$13") (pinfunction "P$13_P$13") (pintype "bidirectional"))
    )
    (net (code "49") (name "unconnected-(S4-PadP$15)") (class "Default")
      (node (ref "S4") (pin "P$15") (pinfunction "P$15_P$15") (pintype "bidirectional"))
    )
    (net (code "50") (name "unconnected-(S4-PadP$17)") (class "Default")
      (node (ref "S4") (pin "P$17") (pinfunction "P$17_P$17") (pintype "bidirectional"))
    )
    (net (code "51") (name "unconnected-(S4-PadP$19)") (class "Default")
      (node (ref "S4") (pin "P$19") (pinfunction "P$19_P$19") (pintype "bidirectional"))
    )
    (net (code "52") (name "unconnected-(S4-PadP$23)") (class "Default")
      (node (ref "S4") (pin "P$23") (pinfunction "P$23_P$23") (pintype "bidirectional"))
    )
    (net (code "53") (name "unconnected-(S5-PadP$3)") (class "Default")
      (node (ref "S5") (pin "P$3") (pinfunction "P$3_P$3") (pintype "bidirectional"))
    )
    (net (code "54") (name "unconnected-(S5-PadP$5)") (class "Default")
      (node (ref "S5") (pin "P$5") (pinfunction "P$5_P$5") (pintype "bidirectional"))
    )
    (net (code "55") (name "unconnected-(S5-PadP$7)") (class "Default")
      (node (ref "S5") (pin "P$7") (pinfunction "P$7_P$7") (pintype "bidirectional"))
    )
    (net (code "56") (name "unconnected-(S5-PadP$9)") (class "Default")
      (node (ref "S5") (pin "P$9") (pinfunction "P$9_P$9") (pintype "bidirectional"))
    )
    (net (code "57") (name "unconnected-(S5-PadP$11)") (class "Default")
      (node (ref "S5") (pin "P$11") (pinfunction "P$11_P$11") (pintype "bidirectional"))
    )
    (net (code "58") (name "unconnected-(S5-PadP$13)") (class "Default")
      (node (ref "S5") (pin "P$13") (pinfunction "P$13_P$13") (pintype "bidirectional"))
    )
    (net (code "59") (name "unconnected-(S5-PadP$15)") (class "Default")
      (node (ref "S5") (pin "P$15") (pinfunction "P$15_P$15") (pintype "bidirectional"))
    )
    (net (code "60") (name "unconnected-(S5-PadP$17)") (class "Default")
      (node (ref "S5") (pin "P$17") (pinfunction "P$17_P$17") (pintype "bidirectional"))
    )
    (net (code "61") (name "unconnected-(S5-PadP$19)") (class "Default")
      (node (ref "S5") (pin "P$19") (pinfunction "P$19_P$19") (pintype "bidirectional"))
    )
    (net (code "62") (name "unconnected-(S5-PadP$23)") (class "Default")
      (node (ref "S5") (pin "P$23") (pinfunction "P$23_P$23") (pintype "bidirectional"))
    )
    (net (code "63") (name "unconnected-(S6-PadP$3)") (class "Default")
      (node (ref "S6") (pin "P$3") (pinfunction "P$3_P$3") (pintype "bidirectional"))
    )
    (net (code "64") (name "unconnected-(S6-PadP$5)") (class "Default")
      (node (ref "S6") (pin "P$5") (pinfunction "P$5_P$5") (pintype "bidirectional"))
    )
    (net (code "65") (name "unconnected-(S6-PadP$7)") (class "Default")
      (node (ref "S6") (pin "P$7") (pinfunction "P$7_P$7") (pintype "bidirectional"))
    )
    (net (code "66") (name "unconnected-(S6-PadP$9)") (class "Default")
      (node (ref "S6") (pin "P$9") (pinfunction "P$9_P$9") (pintype "bidirectional"))
    )
    (net (code "67") (name "unconnected-(S6-PadP$11)") (class "Default")
      (node (ref "S6") (pin "P$11") (pinfunction "P$11_P$11") (pintype "bidirectional"))
    )
    (net (code "68") (name "unconnected-(S6-PadP$13)") (class "Default")
      (node (ref "S6") (pin "P$13") (pinfunction "P$13_P$13") (pintype "bidirectional"))
    )
    (net (code "69") (name "unconnected-(S6-PadP$15)") (class "Default")
      (node (ref "S6") (pin "P$15") (pinfunction "P$15_P$15") (pintype "bidirectional"))
    )
    (net (code "70") (name "unconnected-(S6-PadP$17)") (class "Default")
      (node (ref "S6") (pin "P$17") (pinfunction "P$17_P$17") (pintype "bidirectional"))
    )
    (net (code "71") (name "unconnected-(S6-PadP$19)") (class "Default")
      (node (ref "S6") (pin "P$19") (pinfunction "P$19_P$19") (pintype "bidirectional"))
    )
    (net (code "72") (name "unconnected-(S6-PadP$23)") (class "Default")
      (node (ref "S6") (pin "P$23") (pinfunction "P$23_P$23") (pintype "bidirectional"))
    )
    (net (code "73") (name "unconnected-(S7-PadP$3)") (class "Default")
      (node (ref "S7") (pin "P$3") (pinfunction "P$3_P$3") (pintype "bidirectional"))
    )
    (net (code "74") (name "unconnected-(S7-PadP$5)") (class "Default")
      (node (ref "S7") (pin "P$5") (pinfunction "P$5_P$5") (pintype "bidirectional"))
    )
    (net (code "75") (name "unconnected-(S7-PadP$7)") (class "Default")
      (node (ref "S7") (pin "P$7") (pinfunction "P$7_P$7") (pintype "bidirectional"))
    )
    (net (code "76") (name "unconnected-(S7-PadP$9)") (class "Default")
      (node (ref "S7") (pin "P$9") (pinfunction "P$9_P$9") (pintype "bidirectional"))
    )
    (net (code "77") (name "unconnected-(S7-PadP$11)") (class "Default")
      (node (ref "S7") (pin "P$11") (pinfunction "P$11_P$11") (pintype "bidirectional"))
    )
    (net (code "78") (name "unconnected-(S7-PadP$13)") (class "Default")
      (node (ref "S7") (pin "P$13") (pinfunction "P$13_P$13") (pintype "bidirectional"))
    )
    (net (code "79") (name "unconnected-(S7-PadP$15)") (class "Default")
      (node (ref "S7") (pin "P$15") (pinfunction "P$15_P$15") (pintype "bidirectional"))
    )
    (net (code "80") (name "unconnected-(S7-PadP$17)") (class "Default")
      (node (ref "S7") (pin "P$17") (pinfunction "P$17_P$17") (pintype "bidirectional"))
    )
    (net (code "81") (name "unconnected-(S7-PadP$19)") (class "Default")
      (node (ref "S7") (pin "P$19") (pinfunction "P$19_P$19") (pintype "bidirectional"))
    )
    (net (code "82") (name "unconnected-(S7-PadP$23)") (class "Default")
      (node (ref "S7") (pin "P$23") (pinfunction "P$23_P$23") (pintype "bidirectional"))
    )
    (net (code "83") (name "unconnected-(S8-PadP$3)") (class "Default")
      (node (ref "S8") (pin "P$3") (pinfunction "P$3_P$3") (pintype "bidirectional"))
    )
    (net (code "84") (name "unconnected-(S8-PadP$5)") (class "Default")
      (node (ref "S8") (pin "P$5") (pinfunction "P$5_P$5") (pintype "bidirectional"))
    )
    (net (code "85") (name "unconnected-(S8-PadP$7)") (class "Default")
      (node (ref "S8") (pin "P$7") (pinfunction "P$7_P$7") (pintype "bidirectional"))
    )
    (net (code "86") (name "unconnected-(S8-PadP$9)") (class "Default")
      (node (ref "S8") (pin "P$9") (pinfunction "P$9_P$9") (pintype "bidirectional"))
    )
    (net (code "87") (name "unconnected-(S8-PadP$11)") (class "Default")
      (node (ref "S8") (pin "P$11") (pinfunction "P$11_P$11") (pintype "bidirectional"))
    )
    (net (code "88") (name "unconnected-(S8-PadP$13)") (class "Default")
      (node (ref "S8") (pin "P$13") (pinfunction "P$13_P$13") (pintype "bidirectional"))
    )
    (net (code "89") (name "unconnected-(S8-PadP$15)") (class "Default")
      (node (ref "S8") (pin "P$15") (pinfunction "P$15_P$15") (pintype "bidirectional"))
    )
    (net (code "90") (name "unconnected-(S8-PadP$17)") (class "Default")
      (node (ref "S8") (pin "P$17") (pinfunction "P$17_P$17") (pintype "bidirectional"))
    )
    (net (code "91") (name "unconnected-(S8-PadP$19)") (class "Default")
      (node (ref "S8") (pin "P$19") (pinfunction "P$19_P$19") (pintype "bidirectional"))
    )
    (net (code "92") (name "unconnected-(S8-PadP$23)") (class "Default")
      (node (ref "S8") (pin "P$23") (pinfunction "P$23_P$23") (pintype "bidirectional"))
    )
    (net (code "93") (name "unconnected-(S9-PadP$3)") (class "Default")
      (node (ref "S9") (pin "P$3") (pinfunction "P$3_P$3") (pintype "bidirectional"))
    )
    (net (code "94") (name "unconnected-(S9-PadP$5)") (class "Default")
      (node (ref "S9") (pin "P$5") (pinfunction "P$5_P$5") (pintype "bidirectional"))
    )
    (net (code "95") (name "unconnected-(S9-PadP$7)") (class "Default")
      (node (ref "S9") (pin "P$7") (pinfunction "P$7_P$7") (pintype "bidirectional"))
    )
    (net (code "96") (name "unconnected-(S9-PadP$9)") (class "Default")
      (node (ref "S9") (pin "P$9") (pinfunction "P$9_P$9") (pintype "bidirectional"))
    )
    (net (code "97") (name "unconnected-(S9-PadP$11)") (class "Default")
      (node (ref "S9") (pin "P$11") (pinfunction "P$11_P$11") (pintype "bidirectional"))
    )
    (net (code "98") (name "unconnected-(S9-PadP$13)") (class "Default")
      (node (ref "S9") (pin "P$13") (pinfunction "P$13_P$13") (pintype "bidirectional"))
    )
    (net (code "99") (name "unconnected-(S9-PadP$15)") (class "Default")
      (node (ref "S9") (pin "P$15") (pinfunction "P$15_P$15") (pintype "bidirectional"))
    )
    (net (code "100") (name "unconnected-(S9-PadP$17)") (class "Default")
      (node (ref "S9") (pin "P$17") (pinfunction "P$17_P$17") (pintype "bidirectional"))
    )
    (net (code "101") (name "unconnected-(S9-PadP$19)") (class "Default")
      (node (ref "S9") (pin "P$19") (pinfunction "P$19_P$19") (pintype "bidirectional"))
    )
    (net (code "102") (name "unconnected-(S9-PadP$23)") (class "Default")
      (node (ref "S9") (pin "P$23") (pinfunction "P$23_P$23") (pintype "bidirectional"))
    )
    (net (code "103") (name "unconnected-(S10-PadP$3)") (class "Default")
      (node (ref "S10") (pin "P$3") (pinfunction "P$3_P$3") (pintype "bidirectional"))
    )
    (net (code "104") (name "unconnected-(S10-PadP$5)") (class "Default")
      (node (ref "S10") (pin "P$5") (pinfunction "P$5_P$5") (pintype "bidirectional"))
    )
    (net (code "105") (name "unconnected-(S10-PadP$7)") (class "Default")
      (node (ref "S10") (pin "P$7") (pinfunction "P$7_P$7") (pintype "bidirectional"))
    )
    (net (code "106") (name "unconnected-(S10-PadP$9)") (class "Default")
      (node (ref "S10") (pin "P$9") (pinfunction "P$9_P$9") (pintype "bidirectional"))
    )
    (net (code "107") (name "unconnected-(S10-PadP$11)") (class "Default")
      (node (ref "S10") (pin "P$11") (pinfunction "P$11_P$11") (pintype "bidirectional"))
    )
    (net (code "108") (name "unconnected-(S10-PadP$13)") (class "Default")
      (node (ref "S10") (pin "P$13") (pinfunction "P$13_P$13") (pintype "bidirectional"))
    )
    (net (code "109") (name "unconnected-(S10-PadP$15)") (class "Default")
      (node (ref "S10") (pin "P$15") (pinfunction "P$15_P$15") (pintype "bidirectional"))
    )
    (net (code "110") (name "unconnected-(S10-PadP$17)") (class "Default")
      (node (ref "S10") (pin "P$17") (pinfunction "P$17_P$17") (pintype "bidirectional"))
    )
    (net (code "111") (name "unconnected-(S10-PadP$19)") (class "Default")
      (node (ref "S10") (pin "P$19") (pinfunction "P$19_P$19") (pintype "bidirectional"))
    )
    (net (code "112") (name "unconnected-(S10-PadP$23)") (class "Default")
      (node (ref "S10") (pin "P$23") (pinfunction "P$23_P$23") (pintype "bidirectional"))
    )
    (net (code "113") (name "unconnected-(S11-PadP$3)") (class "Default")
      (node (ref "S11") (pin "P$3") (pinfunction "P$3_P$3") (pintype "bidirectional"))
    )
    (net (code "114") (name "unconnected-(S11-PadP$5)") (class "Default")
      (node (ref "S11") (pin "P$5") (pinfunction "P$5_P$5") (pintype "bidirectional"))
    )
    (net (code "115") (name "unconnected-(S11-PadP$7)") (class "Default")
      (node (ref "S11") (pin "P$7") (pinfunction "P$7_P$7") (pintype "bidirectional"))
    )
    (net (code "116") (name "unconnected-(S11-PadP$9)") (class "Default")
      (node (ref "S11") (pin "P$9") (pinfunction "P$9_P$9") (pintype "bidirectional"))
    )
    (net (code "117") (name "unconnected-(S11-PadP$11)") (class "Default")
      (node (ref "S11") (pin "P$11") (pinfunction "P$11_P$11") (pintype "bidirectional"))
    )
    (net (code "118") (name "unconnected-(S11-PadP$13)") (class "Default")
      (node (ref "S11") (pin "P$13") (pinfunction "P$13_P$13") (pintype "bidirectional"))
    )
    (net (code "119") (name "unconnected-(S11-PadP$15)") (class "Default")
      (node (ref "S11") (pin "P$15") (pinfunction "P$15_P$15") (pintype "bidirectional"))
    )
    (net (code "120") (name "unconnected-(S11-PadP$17)") (class "Default")
      (node (ref "S11") (pin "P$17") (pinfunction "P$17_P$17") (pintype "bidirectional"))
    )
    (net (code "121") (name "unconnected-(S11-PadP$19)") (class "Default")
      (node (ref "S11") (pin "P$19") (pinfunction "P$19_P$19") (pintype "bidirectional"))
    )
    (net (code "122") (name "unconnected-(S11-PadP$23)") (class "Default")
      (node (ref "S11") (pin "P$23") (pinfunction "P$23_P$23") (pintype "bidirectional"))
    )
    (net (code "123") (name "unconnected-(S12-PadP$5)") (class "Default")
      (node (ref "S12") (pin "P$5") (pinfunction "P$5_P$5") (pintype "bidirectional"))
    )
    (net (code "124") (name "unconnected-(S12-PadP$7)") (class "Default")
      (node (ref "S12") (pin "P$7") (pinfunction "P$7_P$7") (pintype "bidirectional"))
    )
    (net (code "125") (name "unconnected-(S12-PadP$9)") (class "Default")
      (node (ref "S12") (pin "P$9") (pinfunction "P$9_P$9") (pintype "bidirectional"))
    )
    (net (code "126") (name "unconnected-(S12-PadP$11)") (class "Default")
      (node (ref "S12") (pin "P$11") (pinfunction "P$11_P$11") (pintype "bidirectional"))
    )
    (net (code "127") (name "unconnected-(S12-PadP$13)") (class "Default")
      (node (ref "S12") (pin "P$13") (pinfunction "P$13_P$13") (pintype "bidirectional"))
    )
    (net (code "128") (name "unconnected-(S12-PadP$15)") (class "Default")
      (node (ref "S12") (pin "P$15") (pinfunction "P$15_P$15") (pintype "bidirectional"))
    )
    (net (code "129") (name "unconnected-(S12-PadP$17)") (class "Default")
      (node (ref "S12") (pin "P$17") (pinfunction "P$17_P$17") (pintype "bidirectional"))
    )
    (net (code "130") (name "unconnected-(S12-PadP$19)") (class "Default")
      (node (ref "S12") (pin "P$19") (pinfunction "P$19_P$19") (pintype "bidirectional"))
    )
    (net (code "131") (name "unconnected-(S12-PadP$23)") (class "Default")
      (node (ref "S12") (pin "P$23") (pinfunction "P$23_P$23") (pintype "bidirectional"))
    )
    (net (code "132") (name "unconnected-(S13-PadP$3)") (class "Default")
      (node (ref "S13") (pin "P$3") (pinfunction "P$3_P$3") (pintype "bidirectional"))
    )
    (net (code "133") (name "unconnected-(S13-PadP$5)") (class "Default")
      (node (ref "S13") (pin "P$5") (pinfunction "P$5_P$5") (pintype "bidirectional"))
    )
    (net (code "134") (name "unconnected-(S13-PadP$7)") (class "Default")
      (node (ref "S13") (pin "P$7") (pinfunction "P$7_P$7") (pintype "bidirectional"))
    )
    (net (code "135") (name "unconnected-(S13-PadP$9)") (class "Default")
      (node (ref "S13") (pin "P$9") (pinfunction "P$9_P$9") (pintype "bidirectional"))
    )
    (net (code "136") (name "unconnected-(S13-PadP$11)") (class "Default")
      (node (ref "S13") (pin "P$11") (pinfunction "P$11_P$11") (pintype "bidirectional"))
    )
    (net (code "137") (name "unconnected-(S13-PadP$13)") (class "Default")
      (node (ref "S13") (pin "P$13") (pinfunction "P$13_P$13") (pintype "bidirectional"))
    )
    (net (code "138") (name "unconnected-(S13-PadP$15)") (class "Default")
      (node (ref "S13") (pin "P$15") (pinfunction "P$15_P$15") (pintype "bidirectional"))
    )
    (net (code "139") (name "unconnected-(S13-PadP$17)") (class "Default")
      (node (ref "S13") (pin "P$17") (pinfunction "P$17_P$17") (pintype "bidirectional"))
    )
    (net (code "140") (name "unconnected-(S13-PadP$19)") (class "Default")
      (node (ref "S13") (pin "P$19") (pinfunction "P$19_P$19") (pintype "bidirectional"))
    )
    (net (code "141") (name "unconnected-(S13-PadP$23)") (class "Default")
      (node (ref "S13") (pin "P$23") (pinfunction "P$23_P$23") (pintype "bidirectional"))
    )
    (net (code "142") (name "unconnected-(S14-PadP$3)") (class "Default")
      (node (ref "S14") (pin "P$3") (pinfunction "P$3_P$3") (pintype "bidirectional"))
    )
    (net (code "143") (name "unconnected-(S14-PadP$5)") (class "Default")
      (node (ref "S14") (pin "P$5") (pinfunction "P$5_P$5") (pintype "bidirectional"))
    )
    (net (code "144") (name "unconnected-(S14-PadP$7)") (class "Default")
      (node (ref "S14") (pin "P$7") (pinfunction "P$7_P$7") (pintype "bidirectional"))
    )
    (net (code "145") (name "unconnected-(S14-PadP$9)") (class "Default")
      (node (ref "S14") (pin "P$9") (pinfunction "P$9_P$9") (pintype "bidirectional"))
    )
    (net (code "146") (name "unconnected-(S14-PadP$11)") (class "Default")
      (node (ref "S14") (pin "P$11") (pinfunction "P$11_P$11") (pintype "bidirectional"))
    )
    (net (code "147") (name "unconnected-(S14-PadP$13)") (class "Default")
      (node (ref "S14") (pin "P$13") (pinfunction "P$13_P$13") (pintype "bidirectional"))
    )
    (net (code "148") (name "unconnected-(S14-PadP$15)") (class "Default")
      (node (ref "S14") (pin "P$15") (pinfunction "P$15_P$15") (pintype "bidirectional"))
    )
    (net (code "149") (name "unconnected-(S14-PadP$17)") (class "Default")
      (node (ref "S14") (pin "P$17") (pinfunction "P$17_P$17") (pintype "bidirectional"))
    )
    (net (code "150") (name "unconnected-(S14-PadP$19)") (class "Default")
      (node (ref "S14") (pin "P$19") (pinfunction "P$19_P$19") (pintype "bidirectional"))
    )
    (net (code "151") (name "unconnected-(S14-PadP$23)") (class "Default")
      (node (ref "S14") (pin "P$23") (pinfunction "P$23_P$23") (pintype "bidirectional"))
    )
  )
)
